# Power.net
KiCad netlist of a schematic drawn in Altium Designer
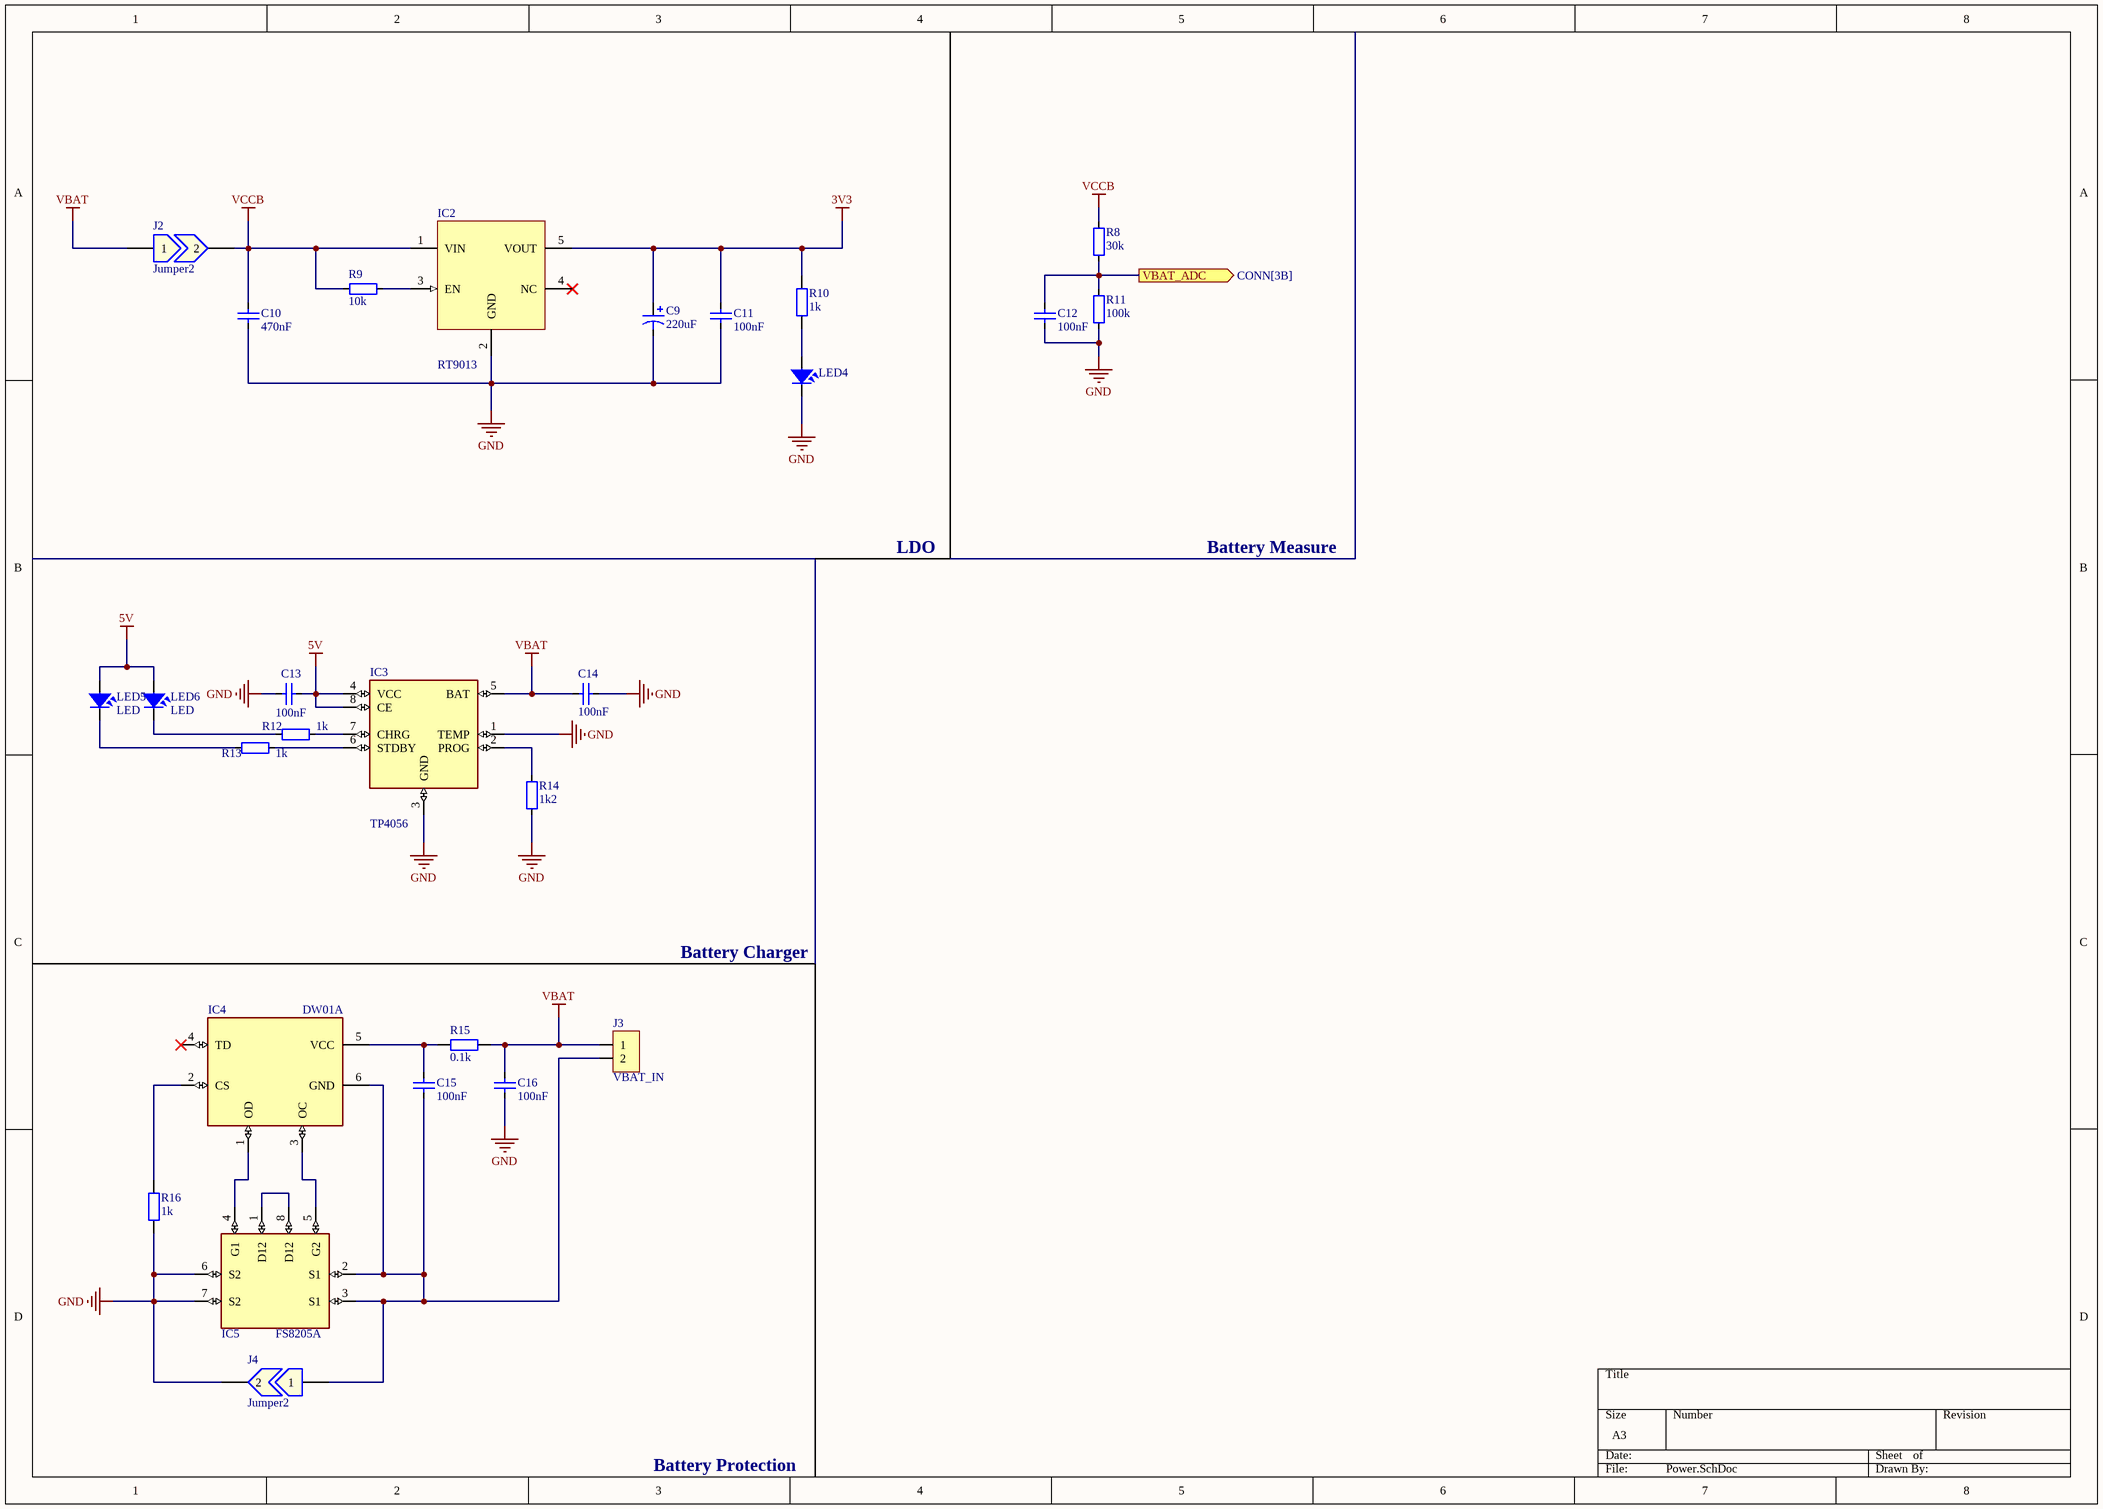
[diagram p0: Power.SchDoc]

(export (version "E")
  (design (tool "Eeschema 10.0.6"))
  (components
    (comp (ref "C9")
      (value "220uF")
      (footprint "CAP_TANTALUM_3216")
      (description "Polarized Capacitor (Axial)")
      (fields (field (name "PUBLISHER") "Altium Limited"))
      (libsource (lib "My Library") (part "Cap Pol"))
    )
    (comp (ref "C10")
      (value "470nF")
      (footprint "CAP_0805")
      (description "Capacitor")
      (fields (field (name "PUBLISHER") "Altium Limited"))
      (libsource (lib "My Library") (part "CapSMD"))
    )
    (comp (ref "C11")
      (value "100nF")
      (footprint "CAP_0805")
      (description "Capacitor")
      (fields (field (name "PUBLISHER") "Altium Limited"))
      (libsource (lib "My Library") (part "CapSMD"))
    )
    (comp (ref "C12")
      (value "100nF")
      (footprint "CAP_0805")
      (description "Capacitor")
      (fields (field (name "PUBLISHER") "Altium Limited"))
      (libsource (lib "My Library") (part "CapSMD"))
    )
    (comp (ref "C13")
      (value "100nF")
      (footprint "CAP_0805")
      (description "Capacitor")
      (fields (field (name "PUBLISHER") "Altium Limited"))
      (libsource (lib "My Library") (part "CapSMD"))
    )
    (comp (ref "C14")
      (value "100nF")
      (footprint "CAP_0805")
      (description "Capacitor")
      (fields (field (name "PUBLISHER") "Altium Limited"))
      (libsource (lib "My Library") (part "CapSMD"))
    )
    (comp (ref "C15")
      (value "100nF")
      (footprint "CAP_0805")
      (description "Capacitor")
      (fields (field (name "PUBLISHER") "Altium Limited"))
      (libsource (lib "My Library") (part "CapSMD"))
    )
    (comp (ref "C16")
      (value "100nF")
      (footprint "CAP_0805")
      (description "Capacitor")
      (fields (field (name "PUBLISHER") "Altium Limited"))
      (libsource (lib "My Library") (part "CapSMD"))
    )
    (comp (ref "IC2")
      (value "RT9013")
      (footprint "SOT23-5")
      (description "https://linhkien.cxt.vn/5435-rt9013-33gb-ic-reg-linear-33v-500ma-sot23-5.html")
      (libsource (lib "My Library") (part "RT9013"))
    )
    (comp (ref "IC3")
      (value "TP4056")
      (footprint "TP4056")
      (description "Complete single cell Li-Ion battery with a constant current / constant voltage linear charger")
      (libsource (lib "My Library") (part "TP4056"))
    )
    (comp (ref "IC4")
      (value "DW01A")
      (footprint "SOT23-6")
      (description "One Cell Lithium-ion/Polymer Battery Protection IC")
      (libsource (lib "My Library") (part "DW01A"))
    )
    (comp (ref "IC5") (value "FS8205A") (footprint "FS8205A") (libsource (lib "My Library") (part "FS8205A")))
    (comp (ref "J2")
      (value "Jumper2")
      (footprint "JUMPER2")
      (description "Jumper, 2-Pin")
      (libsource (lib "Main") (part "Jumper2"))
    )
    (comp (ref "J3")
      (value "VBAT_IN")
      (footprint "JP2-D1T")
      (description "WR-PHD 2.54 mm Angled Socket Header")
      (fields
        (field (name "MANUFACTURER") "Würth Elektronik eiSos GmbH")
        (field (name "PARTNO") "613002143121")
        (field (name "CREATED BY") "Karrer Zheng")
      )
      (libsource (lib "My Library") (part "JP2"))
    )
    (comp (ref "J4")
      (value "Jumper2")
      (footprint "RES-SMD-0201")
      (description "Jumper, 2-Pin")
      (libsource (lib "My Library") (part "Jumper2"))
    )
    (comp (ref "LED4")
      (value "~")
      (footprint "LED-0805-Red")
      (description "LED Single colour Green and Red")
      (libsource (lib "Main") (part "LED"))
    )
    (comp (ref "LED5")
      (value "LED")
      (footprint "LED-0805-Red")
      (description "LED Single colour Green and Red")
      (libsource (lib "My Library") (part "LED"))
    )
    (comp (ref "LED6")
      (value "LED")
      (footprint "LED-0805-Green")
      (description "LED Single colour Green and Red")
      (libsource (lib "My Library") (part "LED"))
    )
    (comp (ref "R8")
      (value "30k")
      (footprint "RES-SMD-0805")
      (description "Resistor")
      (fields
        (field (name "MANUFACTURER") "Generic Components")
        (field (name "PUBLISHER") "Altium Hobart Technology Centre")
      )
      (libsource (lib "My Library") (part "Resistor - SMD"))
    )
    (comp (ref "R9")
      (value "10k")
      (footprint "RES-SMD-0805")
      (description "Resistor")
      (fields
        (field (name "MANUFACTURER") "Generic Components")
        (field (name "PUBLISHER") "Altium Hobart Technology Centre")
      )
      (libsource (lib "My Library") (part "Resistor - SMD"))
    )
    (comp (ref "R10")
      (value "1k")
      (footprint "RES-SMD-0805")
      (description "Resistor SMD")
      (fields
        (field (name "MANUFACTURER") "Generic Components")
        (field (name "PUBLISHER") "Altium Hobart Technology Centre")
      )
      (libsource (lib "Main") (part "Resistor - SMD"))
    )
    (comp (ref "R11")
      (value "100k")
      (footprint "RES-SMD-0805")
      (description "Resistor")
      (fields
        (field (name "MANUFACTURER") "Generic Components")
        (field (name "PUBLISHER") "Altium Hobart Technology Centre")
      )
      (libsource (lib "My Library") (part "Resistor - SMD"))
    )
    (comp (ref "R12")
      (value "1k")
      (footprint "RES-SMD-0805")
      (description "Resistor")
      (fields
        (field (name "MANUFACTURER") "Generic Components")
        (field (name "PUBLISHER") "Altium Hobart Technology Centre")
      )
      (libsource (lib "My Library") (part "Resistor - SMD"))
    )
    (comp (ref "R13")
      (value "1k")
      (footprint "RES-SMD-0805")
      (description "Resistor")
      (fields
        (field (name "MANUFACTURER") "Generic Components")
        (field (name "PUBLISHER") "Altium Hobart Technology Centre")
      )
      (libsource (lib "My Library") (part "Resistor - SMD"))
    )
    (comp (ref "R14")
      (value "1k2")
      (footprint "RES-SMD-0805")
      (description "Resistor")
      (fields
        (field (name "MANUFACTURER") "Generic Components")
        (field (name "PUBLISHER") "Altium Hobart Technology Centre")
      )
      (libsource (lib "My Library") (part "Resistor - SMD"))
    )
    (comp (ref "R15")
      (value "0.1k")
      (footprint "RES-SMD-0805")
      (description "Resistor SMD")
      (fields
        (field (name "MANUFACTURER") "Generic Components")
        (field (name "PUBLISHER") "Altium Hobart Technology Centre")
      )
      (libsource (lib "") (part "Resistor - SMD_1"))
    )
    (comp (ref "R16")
      (value "1k")
      (footprint "RES-SMD-0805")
      (description "Resistor SMD")
      (fields
        (field (name "MANUFACTURER") "Generic Components")
        (field (name "PUBLISHER") "Altium Hobart Technology Centre")
      )
      (libsource (lib "") (part "Resistor - SMD_1"))
    )
  )
  (nets
    (net (code "1") (name "/VBAT_ADC") (class "Default")
      (node (ref "C12") (pin "2") (pinfunction "2_2") (pintype "passive"))
      (node (ref "R11") (pin "1") (pinfunction "1_1") (pintype "passive"))
      (node (ref "R8") (pin "2") (pinfunction "2_2") (pintype "passive"))
    )
    (net (code "2") (name "3V3") (class "Default")
      (node (ref "C11") (pin "1") (pinfunction "1_1") (pintype "passive"))
      (node (ref "C9") (pin "1") (pinfunction "1_1") (pintype "passive"))
      (node (ref "IC2") (pin "5") (pinfunction "VOUT_5") (pintype "power_in"))
      (node (ref "R10") (pin "2") (pinfunction "2_2") (pintype "passive"))
    )
    (net (code "3") (name "5V") (class "Default")
      (node (ref "C13") (pin "1") (pinfunction "1_1") (pintype "passive"))
      (node (ref "IC3") (pin "4") (pinfunction "VCC_4") (pintype "bidirectional"))
      (node (ref "IC3") (pin "8") (pinfunction "CE_8") (pintype "bidirectional"))
      (node (ref "LED5") (pin "1") (pinfunction "1_1") (pintype "passive"))
      (node (ref "LED6") (pin "1") (pinfunction "1_1") (pintype "passive"))
    )
    (net (code "4") (name "GND") (class "Default")
      (node (ref "C10") (pin "2") (pinfunction "2_2") (pintype "passive"))
      (node (ref "C11") (pin "2") (pinfunction "2_2") (pintype "passive"))
      (node (ref "C12") (pin "1") (pinfunction "1_1") (pintype "passive"))
      (node (ref "C13") (pin "2") (pinfunction "2_2") (pintype "passive"))
      (node (ref "C14") (pin "1") (pinfunction "1_1") (pintype "passive"))
      (node (ref "C16") (pin "1") (pinfunction "1_1") (pintype "passive"))
      (node (ref "C9") (pin "2") (pinfunction "2_2") (pintype "passive"))
      (node (ref "IC2") (pin "2") (pinfunction "GND_2") (pintype "power_in"))
      (node (ref "IC3") (pin "1") (pinfunction "TEMP_1") (pintype "bidirectional"))
      (node (ref "IC3") (pin "3") (pinfunction "GND_3") (pintype "bidirectional"))
      (node (ref "IC5") (pin "6") (pinfunction "S2_6") (pintype "bidirectional"))
      (node (ref "IC5") (pin "7") (pinfunction "S2_7") (pintype "bidirectional"))
      (node (ref "J4") (pin "2") (pinfunction "2_2") (pintype "passive"))
      (node (ref "LED4") (pin "2") (pinfunction "2_2") (pintype "passive"))
      (node (ref "R11") (pin "2") (pinfunction "2_2") (pintype "passive"))
      (node (ref "R14") (pin "1") (pinfunction "1_1") (pintype "passive"))
      (node (ref "R16") (pin "2") (pinfunction "2_2") (pintype "passive"))
    )
    (net (code "5") (name "Net-(IC2-EN)") (class "Default")
      (node (ref "IC2") (pin "3") (pinfunction "EN_3") (pintype "input"))
      (node (ref "R9") (pin "1") (pinfunction "1_1") (pintype "passive"))
    )
    (net (code "6") (name "Net-(IC3-CHRG)") (class "Default")
      (node (ref "IC3") (pin "7") (pinfunction "CHRG_7") (pintype "bidirectional"))
      (node (ref "R12") (pin "1") (pinfunction "1_1") (pintype "passive"))
    )
    (net (code "7") (name "Net-(IC3-PROG)") (class "Default")
      (node (ref "IC3") (pin "2") (pinfunction "PROG_2") (pintype "bidirectional"))
      (node (ref "R14") (pin "2") (pinfunction "2_2") (pintype "passive"))
    )
    (net (code "8") (name "Net-(IC3-STDBY)") (class "Default")
      (node (ref "IC3") (pin "6") (pinfunction "STDBY_6") (pintype "bidirectional"))
      (node (ref "R13") (pin "1") (pinfunction "1_1") (pintype "passive"))
    )
    (net (code "9") (name "Net-(IC4-CS)") (class "Default")
      (node (ref "IC4") (pin "2") (pinfunction "CS_2") (pintype "bidirectional"))
      (node (ref "R16") (pin "1") (pinfunction "1_1") (pintype "passive"))
    )
    (net (code "10") (name "Net-(IC4-GND)") (class "Default")
      (node (ref "C15") (pin "1") (pinfunction "1_1") (pintype "passive"))
      (node (ref "IC4") (pin "6") (pinfunction "GND_6") (pintype "power_in"))
      (node (ref "IC5") (pin "2") (pinfunction "S1_2") (pintype "bidirectional"))
      (node (ref "IC5") (pin "3") (pinfunction "S1_3") (pintype "bidirectional"))
      (node (ref "J3") (pin "2") (pinfunction "2_2") (pintype "passive"))
      (node (ref "J4") (pin "1") (pinfunction "1_1") (pintype "passive"))
    )
    (net (code "11") (name "Net-(IC4-OC)") (class "Default")
      (node (ref "IC4") (pin "3") (pinfunction "OC_3") (pintype "bidirectional"))
      (node (ref "IC5") (pin "5") (pinfunction "G2_5") (pintype "bidirectional"))
    )
    (net (code "12") (name "Net-(IC4-OD)") (class "Default")
      (node (ref "IC4") (pin "1") (pinfunction "OD_1") (pintype "bidirectional"))
      (node (ref "IC5") (pin "4") (pinfunction "G1_4") (pintype "bidirectional"))
    )
    (net (code "13") (name "Net-(IC4-VCC)") (class "Default")
      (node (ref "C15") (pin "2") (pinfunction "2_2") (pintype "passive"))
      (node (ref "IC4") (pin "5") (pinfunction "VCC_5") (pintype "power_in"))
      (node (ref "R15") (pin "1") (pinfunction "1_1") (pintype "passive"))
    )
    (net (code "14") (name "Net-(IC5-D12-Pad1)") (class "Default")
      (node (ref "IC5") (pin "1") (pinfunction "D12_1") (pintype "bidirectional"))
      (node (ref "IC5") (pin "8") (pinfunction "D12_8") (pintype "bidirectional"))
    )
    (net (code "15") (name "Net-(LED4-Pad1)") (class "Default")
      (node (ref "LED4") (pin "1") (pinfunction "1_1") (pintype "passive"))
      (node (ref "R10") (pin "1") (pinfunction "1_1") (pintype "passive"))
    )
    (net (code "16") (name "Net-(LED5-Pad2)") (class "Default")
      (node (ref "LED5") (pin "2") (pinfunction "2_2") (pintype "passive"))
      (node (ref "R13") (pin "2") (pinfunction "2_2") (pintype "passive"))
    )
    (net (code "17") (name "Net-(LED6-Pad2)") (class "Default")
      (node (ref "LED6") (pin "2") (pinfunction "2_2") (pintype "passive"))
      (node (ref "R12") (pin "2") (pinfunction "2_2") (pintype "passive"))
    )
    (net (code "18") (name "VBAT") (class "Default")
      (node (ref "C14") (pin "2") (pinfunction "2_2") (pintype "passive"))
      (node (ref "C16") (pin "2") (pinfunction "2_2") (pintype "passive"))
      (node (ref "IC3") (pin "5") (pinfunction "BAT_5") (pintype "bidirectional"))
      (node (ref "J2") (pin "1") (pinfunction "1_1") (pintype "passive"))
      (node (ref "J3") (pin "1") (pinfunction "1_1") (pintype "passive"))
      (node (ref "R15") (pin "2") (pinfunction "2_2") (pintype "passive"))
    )
    (net (code "19") (name "VCCB") (class "Default")
      (node (ref "C10") (pin "1") (pinfunction "1_1") (pintype "passive"))
      (node (ref "IC2") (pin "1") (pinfunction "VIN_1") (pintype "power_in"))
      (node (ref "J2") (pin "2") (pinfunction "2_2") (pintype "passive"))
      (node (ref "R8") (pin "1") (pinfunction "1_1") (pintype "passive"))
      (node (ref "R9") (pin "2") (pinfunction "2_2") (pintype "passive"))
    )
    (net (code "20") (name "unconnected-(IC2-NC-Pad4)") (class "Default")
      (node (ref "IC2") (pin "4") (pinfunction "NC_4") (pintype "passive+no_connect"))
    )
    (net (code "21") (name "unconnected-(IC4-TD-Pad4)") (class "Default")
      (node (ref "IC4") (pin "4") (pinfunction "TD_4") (pintype "bidirectional+no_connect"))
    )
  )
)
